# 508_outin_imp.net
KiCad netlist of a schematic drawn in EAGLE
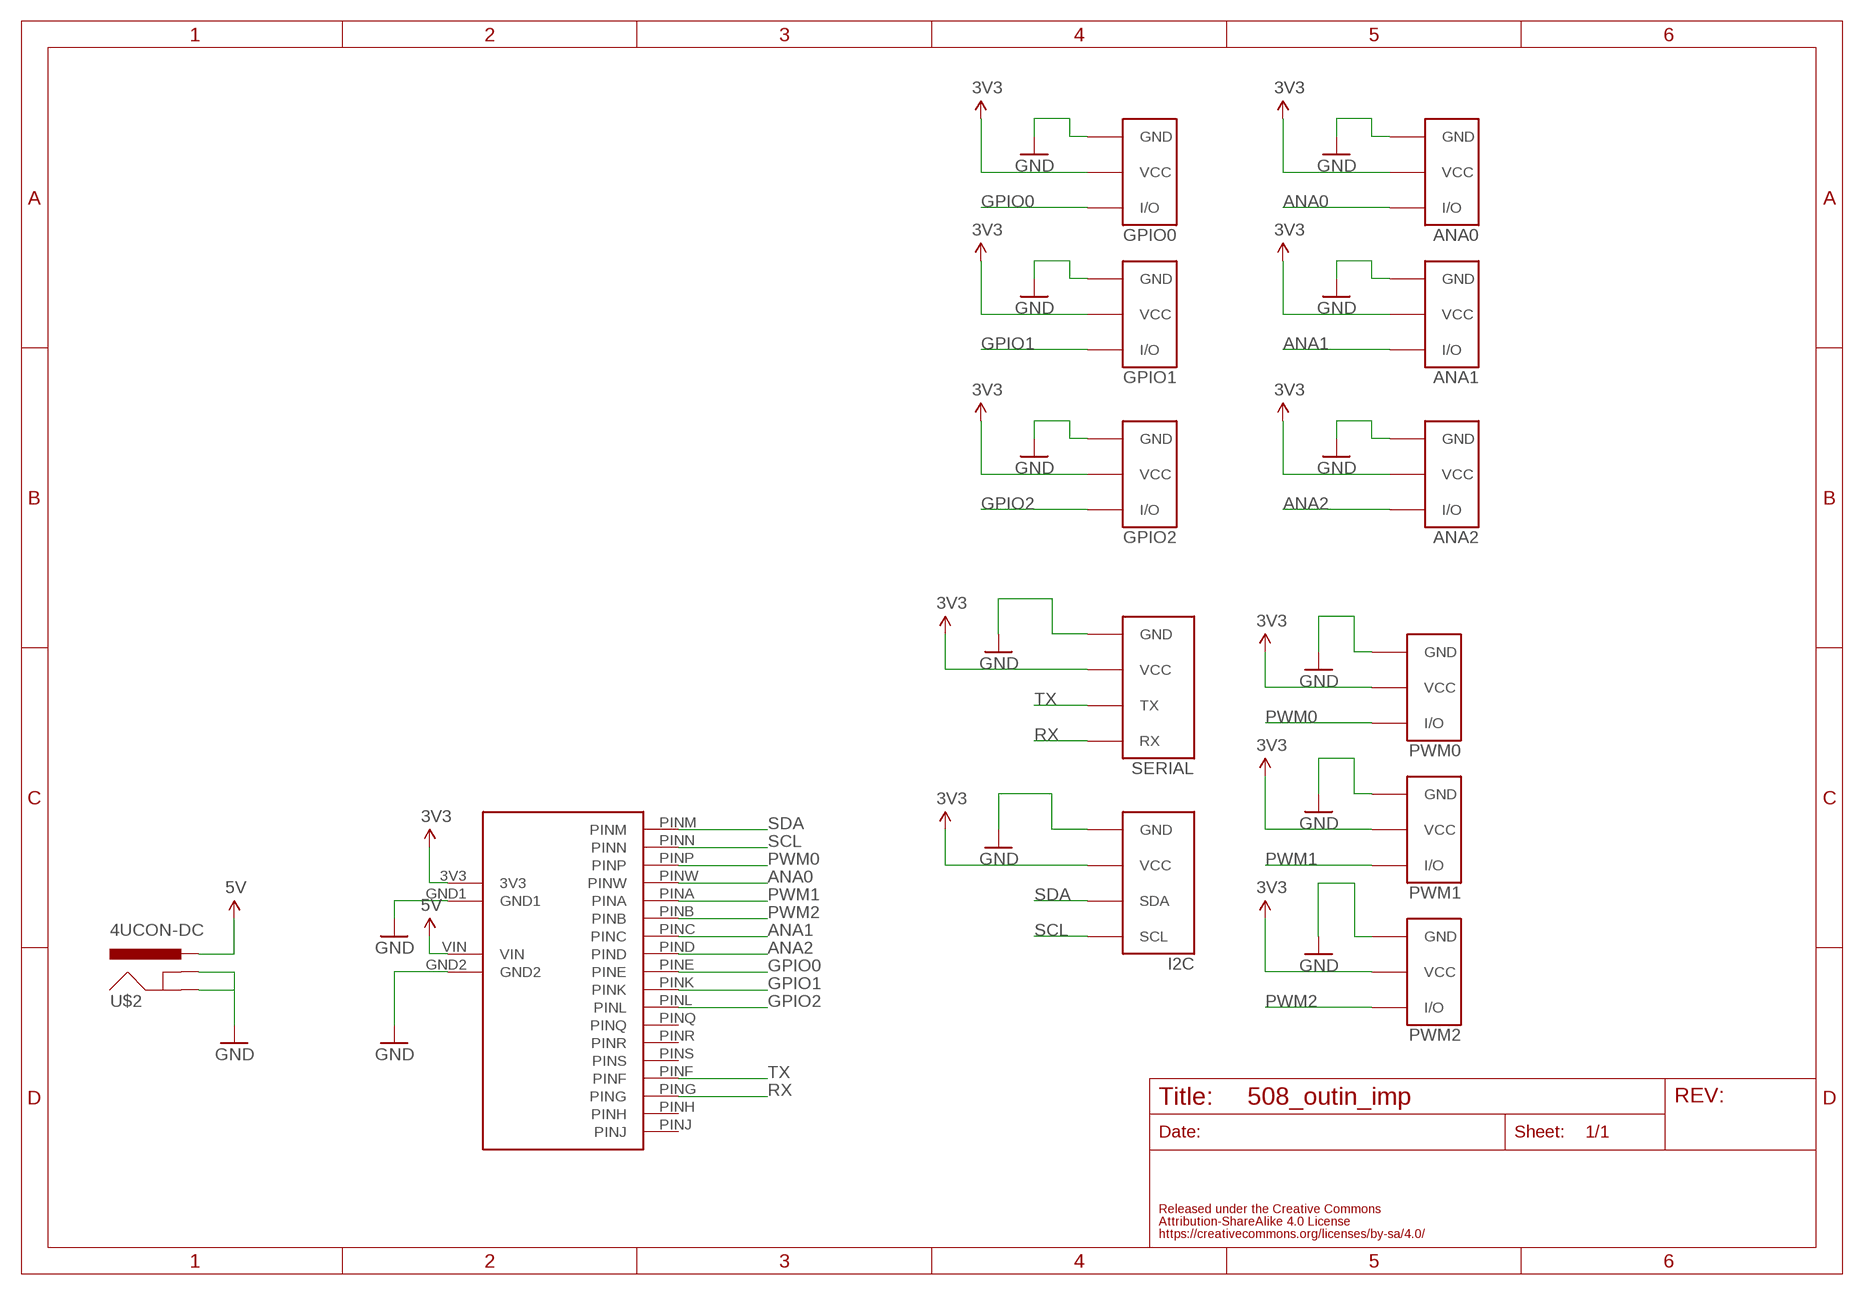
[diagram p0: schematic, sheet 1]

(export (version "E")
  (design (tool "Eeschema 10.0.6"))
  (components
    (comp (ref "ANA0")
      (value "FABO_BRICK_3PIN-B03B-PASK-1_SILK")
      (footprint "eagle-import:FABO_BRICK_3PIN_B03B-PASK-1_SILK")
      (libsource (lib "eagle-import") (part "FABO_BRICK_3PIN-B03B-PASK-1_SILK"))
    )
    (comp (ref "ANA1")
      (value "FABO_BRICK_3PIN-B03B-PASK-1_SILK")
      (footprint "eagle-import:FABO_BRICK_3PIN_B03B-PASK-1_SILK")
      (libsource (lib "eagle-import") (part "FABO_BRICK_3PIN-B03B-PASK-1_SILK"))
    )
    (comp (ref "ANA2")
      (value "FABO_BRICK_3PIN-B03B-PASK-1_SILK")
      (footprint "eagle-import:FABO_BRICK_3PIN_B03B-PASK-1_SILK")
      (libsource (lib "eagle-import") (part "FABO_BRICK_3PIN-B03B-PASK-1_SILK"))
    )
    (comp (ref "GPIO0")
      (value "FABO_BRICK_3PIN-B03B-PASK-1_SILK")
      (footprint "eagle-import:FABO_BRICK_3PIN_B03B-PASK-1_SILK")
      (libsource (lib "eagle-import") (part "FABO_BRICK_3PIN-B03B-PASK-1_SILK"))
    )
    (comp (ref "GPIO1")
      (value "FABO_BRICK_3PIN-B03B-PASK-1_SILK")
      (footprint "eagle-import:FABO_BRICK_3PIN_B03B-PASK-1_SILK")
      (libsource (lib "eagle-import") (part "FABO_BRICK_3PIN-B03B-PASK-1_SILK"))
    )
    (comp (ref "GPIO2")
      (value "FABO_BRICK_3PIN-B03B-PASK-1_SILK")
      (footprint "eagle-import:FABO_BRICK_3PIN_B03B-PASK-1_SILK")
      (libsource (lib "eagle-import") (part "FABO_BRICK_3PIN-B03B-PASK-1_SILK"))
    )
    (comp (ref "I2C")
      (value "FABO_BRICK_I2C-S04B-PASK-2_LONG")
      (footprint "eagle-import:FABO_BRICK_I2C_S04B-PASK-2_LONG")
      (libsource (lib "eagle-import") (part "FABO_BRICK_I2C-S04B-PASK-2_LONG"))
    )
    (comp (ref "PWM0")
      (value "FABO_BRICK_3PIN-HEADER")
      (footprint "eagle-import:FABO_BRICK_3PIN_HEADER")
      (libsource (lib "eagle-import") (part "FABO_BRICK_3PIN-HEADER"))
    )
    (comp (ref "PWM1")
      (value "FABO_BRICK_3PIN-HEADER")
      (footprint "eagle-import:FABO_BRICK_3PIN_HEADER")
      (libsource (lib "eagle-import") (part "FABO_BRICK_3PIN-HEADER"))
    )
    (comp (ref "PWM2")
      (value "FABO_BRICK_3PIN-HEADER")
      (footprint "eagle-import:FABO_BRICK_3PIN_HEADER")
      (libsource (lib "eagle-import") (part "FABO_BRICK_3PIN-HEADER"))
    )
    (comp (ref "SERIAL")
      (value "FABO_BRICK_SERIAL-S04B-PASK-2_LONG")
      (footprint "eagle-import:FABO_BRICK_SERIAL_S04B-PASK-2_LONG")
      (libsource (lib "eagle-import") (part "FABO_BRICK_SERIAL-S04B-PASK-2_LONG"))
    )
    (comp (ref "U$1")
      (value "FABO-IMP")
      (footprint "eagle-import:FABO-IMP")
      (libsource (lib "eagle-import") (part "FABO-IMP"))
    )
    (comp (ref "U$2")
      (value "4UCON-DC")
      (footprint "eagle-import:4UCON-DC")
      (libsource (lib "eagle-import") (part "4UCON-DC"))
    )
  )
  (nets
    (net (code "1") (name "/ANA0") (class "Default")
      (node (ref "ANA0") (pin "I/O") (pinfunction "I/O_I/O") (pintype "bidirectional"))
      (node (ref "U$1") (pin "PINW") (pinfunction "PINW_PINW") (pintype "bidirectional"))
    )
    (net (code "2") (name "/ANA1") (class "Default")
      (node (ref "ANA1") (pin "I/O") (pinfunction "I/O_I/O") (pintype "bidirectional"))
      (node (ref "U$1") (pin "PINC") (pinfunction "PINC_PINC") (pintype "bidirectional"))
    )
    (net (code "3") (name "/ANA2") (class "Default")
      (node (ref "ANA2") (pin "I/O") (pinfunction "I/O_I/O") (pintype "bidirectional"))
      (node (ref "U$1") (pin "PIND") (pinfunction "PIND_PIND") (pintype "bidirectional"))
    )
    (net (code "4") (name "/GPIO0") (class "Default")
      (node (ref "GPIO0") (pin "I/O") (pinfunction "I/O_I/O") (pintype "bidirectional"))
      (node (ref "U$1") (pin "PINE") (pinfunction "PINE_PINE") (pintype "bidirectional"))
    )
    (net (code "5") (name "/GPIO1") (class "Default")
      (node (ref "GPIO1") (pin "I/O") (pinfunction "I/O_I/O") (pintype "bidirectional"))
      (node (ref "U$1") (pin "PINK") (pinfunction "PINK_PINK") (pintype "bidirectional"))
    )
    (net (code "6") (name "/GPIO2") (class "Default")
      (node (ref "GPIO2") (pin "I/O") (pinfunction "I/O_I/O") (pintype "bidirectional"))
      (node (ref "U$1") (pin "PINL") (pinfunction "PINL_PINL") (pintype "bidirectional"))
    )
    (net (code "7") (name "/PWM0") (class "Default")
      (node (ref "PWM0") (pin "I/O") (pinfunction "I/O_I/O") (pintype "bidirectional"))
      (node (ref "U$1") (pin "PINP") (pinfunction "PINP_PINP") (pintype "bidirectional"))
    )
    (net (code "8") (name "/PWM1") (class "Default")
      (node (ref "PWM1") (pin "I/O") (pinfunction "I/O_I/O") (pintype "bidirectional"))
      (node (ref "U$1") (pin "PINA") (pinfunction "PINA_PINA") (pintype "bidirectional"))
    )
    (net (code "9") (name "/PWM2") (class "Default")
      (node (ref "PWM2") (pin "I/O") (pinfunction "I/O_I/O") (pintype "bidirectional"))
      (node (ref "U$1") (pin "PINB") (pinfunction "PINB_PINB") (pintype "bidirectional"))
    )
    (net (code "10") (name "/RX") (class "Default")
      (node (ref "SERIAL") (pin "RX") (pinfunction "RX_RX") (pintype "bidirectional"))
      (node (ref "U$1") (pin "PING") (pinfunction "PING_PING") (pintype "bidirectional"))
    )
    (net (code "11") (name "/SCL") (class "Default")
      (node (ref "I2C") (pin "SCL") (pinfunction "SCL_SCL") (pintype "bidirectional"))
      (node (ref "U$1") (pin "PINN") (pinfunction "PINN_PINN") (pintype "bidirectional"))
    )
    (net (code "12") (name "/SDA") (class "Default")
      (node (ref "I2C") (pin "SDA") (pinfunction "SDA_SDA") (pintype "bidirectional"))
      (node (ref "U$1") (pin "PINM") (pinfunction "PINM_PINM") (pintype "bidirectional"))
    )
    (net (code "13") (name "/TX") (class "Default")
      (node (ref "SERIAL") (pin "TX") (pinfunction "TX_TX") (pintype "bidirectional"))
      (node (ref "U$1") (pin "PINF") (pinfunction "PINF_PINF") (pintype "bidirectional"))
    )
    (net (code "14") (name "3V3") (class "Default")
      (node (ref "ANA0") (pin "VCC") (pinfunction "VCC_VCC") (pintype "bidirectional"))
      (node (ref "ANA1") (pin "VCC") (pinfunction "VCC_VCC") (pintype "bidirectional"))
      (node (ref "ANA2") (pin "VCC") (pinfunction "VCC_VCC") (pintype "bidirectional"))
      (node (ref "GPIO0") (pin "VCC") (pinfunction "VCC_VCC") (pintype "bidirectional"))
      (node (ref "GPIO1") (pin "VCC") (pinfunction "VCC_VCC") (pintype "bidirectional"))
      (node (ref "GPIO2") (pin "VCC") (pinfunction "VCC_VCC") (pintype "bidirectional"))
      (node (ref "I2C") (pin "VCC") (pinfunction "VCC_VCC") (pintype "bidirectional"))
      (node (ref "PWM0") (pin "VCC") (pinfunction "VCC_VCC") (pintype "bidirectional"))
      (node (ref "PWM1") (pin "VCC") (pinfunction "VCC_VCC") (pintype "bidirectional"))
      (node (ref "PWM2") (pin "VCC") (pinfunction "VCC_VCC") (pintype "bidirectional"))
      (node (ref "SERIAL") (pin "VCC") (pinfunction "VCC_VCC") (pintype "bidirectional"))
      (node (ref "U$1") (pin "3V3") (pinfunction "3V3_3V3") (pintype "bidirectional"))
    )
    (net (code "15") (name "5V") (class "Default")
      (node (ref "U$1") (pin "VIN") (pinfunction "VIN_VIN") (pintype "bidirectional"))
      (node (ref "U$2") (pin "VCC") (pinfunction "PWR_VCC") (pintype "bidirectional"))
    )
    (net (code "16") (name "GND") (class "Default")
      (node (ref "ANA0") (pin "GND") (pinfunction "GND_GND") (pintype "bidirectional"))
      (node (ref "ANA1") (pin "GND") (pinfunction "GND_GND") (pintype "bidirectional"))
      (node (ref "ANA2") (pin "GND") (pinfunction "GND_GND") (pintype "bidirectional"))
      (node (ref "GPIO0") (pin "GND") (pinfunction "GND_GND") (pintype "bidirectional"))
      (node (ref "GPIO1") (pin "GND") (pinfunction "GND_GND") (pintype "bidirectional"))
      (node (ref "GPIO2") (pin "GND") (pinfunction "GND_GND") (pintype "bidirectional"))
      (node (ref "I2C") (pin "GND") (pinfunction "GND_GND") (pintype "bidirectional"))
      (node (ref "PWM0") (pin "GND") (pinfunction "GND_GND") (pintype "bidirectional"))
      (node (ref "PWM1") (pin "GND") (pinfunction "GND_GND") (pintype "bidirectional"))
      (node (ref "PWM2") (pin "GND") (pinfunction "GND_GND") (pintype "bidirectional"))
      (node (ref "SERIAL") (pin "GND") (pinfunction "GND_GND") (pintype "bidirectional"))
      (node (ref "U$1") (pin "GND1") (pinfunction "GND1_GND1") (pintype "bidirectional"))
      (node (ref "U$1") (pin "GND2") (pinfunction "GND2_GND2") (pintype "bidirectional"))
      (node (ref "U$2") (pin "GND1") (pinfunction "GND_GND1") (pintype "bidirectional"))
      (node (ref "U$2") (pin "GND2") (pinfunction "GNDBREAK_GND2") (pintype "bidirectional"))
    )
    (net (code "17") (name "unconnected-(U$1-PadPINH)") (class "Default")
      (node (ref "U$1") (pin "PINH") (pinfunction "PINH_PINH") (pintype "bidirectional"))
    )
    (net (code "18") (name "unconnected-(U$1-PadPINJ)") (class "Default")
      (node (ref "U$1") (pin "PINJ") (pinfunction "PINJ_PINJ") (pintype "bidirectional"))
    )
    (net (code "19") (name "unconnected-(U$1-PadPINQ)") (class "Default")
      (node (ref "U$1") (pin "PINQ") (pinfunction "PINQ_PINQ") (pintype "bidirectional"))
    )
    (net (code "20") (name "unconnected-(U$1-PadPINR)") (class "Default")
      (node (ref "U$1") (pin "PINR") (pinfunction "PINR_PINR") (pintype "bidirectional"))
    )
    (net (code "21") (name "unconnected-(U$1-PadPINS)") (class "Default")
      (node (ref "U$1") (pin "PINS") (pinfunction "PINS_PINS") (pintype "bidirectional"))
    )
  )
)
